# base-6u-generic-xau4.net
KiCad netlist of a schematic drawn in EAGLE
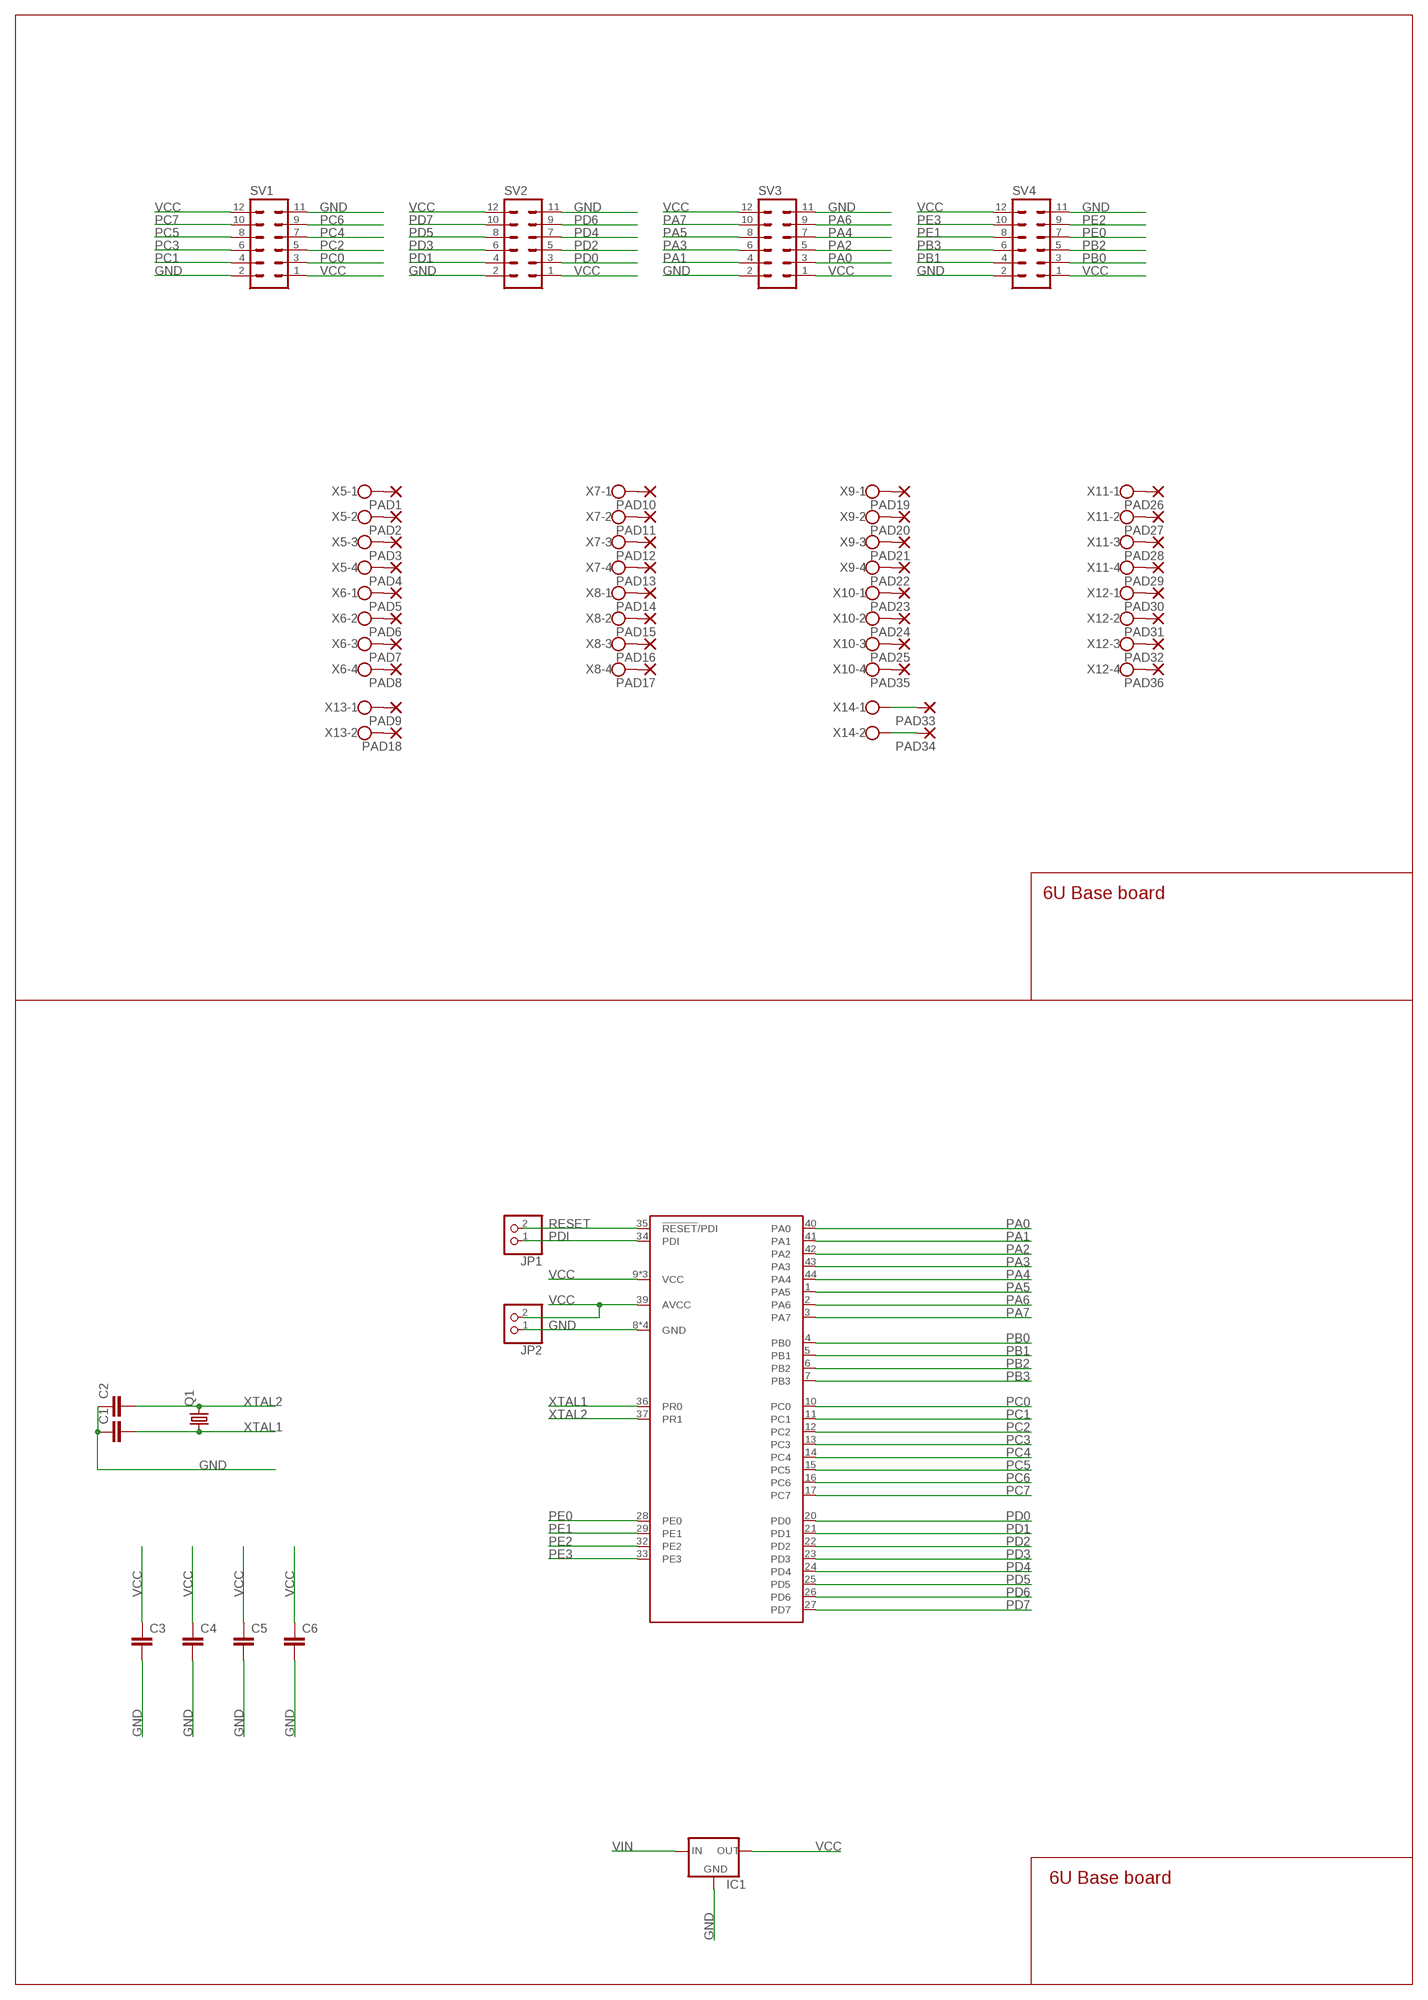
[diagram p0: schematic, sheet 1]

(export (version "E")
  (design (tool "Eeschema 10.0.6"))
  (components
    (comp (ref "C1")
      (value "C-EUC0805")
      (footprint "eagle-import:C0805")
      (libsource (lib "eagle-import") (part "C-EUC0805"))
    )
    (comp (ref "C2")
      (value "C-EUC0805")
      (footprint "eagle-import:C0805")
      (libsource (lib "eagle-import") (part "C-EUC0805"))
    )
    (comp (ref "C3")
      (value "C-EUC0603")
      (footprint "eagle-import:C0603")
      (libsource (lib "eagle-import") (part "C-EUC0603"))
    )
    (comp (ref "C4")
      (value "C-EUC0603")
      (footprint "eagle-import:C0603")
      (libsource (lib "eagle-import") (part "C-EUC0603"))
    )
    (comp (ref "C5")
      (value "C-EUC0603")
      (footprint "eagle-import:C0603")
      (libsource (lib "eagle-import") (part "C-EUC0603"))
    )
    (comp (ref "C6")
      (value "C-EUC0603")
      (footprint "eagle-import:C0603")
      (libsource (lib "eagle-import") (part "C-EUC0603"))
    )
    (comp (ref "IC1")
      (value "LM1117TO252")
      (footprint "eagle-import:TO252")
      (libsource (lib "eagle-import") (part "LM1117TO252"))
    )
    (comp (ref "JP1")
      (value "PINHD-1X2")
      (footprint "eagle-import:1X02")
      (libsource (lib "eagle-import") (part "PINHD-1X2"))
    )
    (comp (ref "JP2")
      (value "PINHD-1X2")
      (footprint "eagle-import:1X02")
      (libsource (lib "eagle-import") (part "PINHD-1X2"))
    )
    (comp (ref "PAD1")
      (value "2,54/0,8")
      (footprint "eagle-import:2,54_0,8")
      (libsource (lib "eagle-import") (part "2,54/0,8"))
    )
    (comp (ref "PAD2")
      (value "2,54/0,8")
      (footprint "eagle-import:2,54_0,8")
      (libsource (lib "eagle-import") (part "2,54/0,8"))
    )
    (comp (ref "PAD3")
      (value "2,54/0,8")
      (footprint "eagle-import:2,54_0,8")
      (libsource (lib "eagle-import") (part "2,54/0,8"))
    )
    (comp (ref "PAD4")
      (value "2,54/0,8")
      (footprint "eagle-import:2,54_0,8")
      (libsource (lib "eagle-import") (part "2,54/0,8"))
    )
    (comp (ref "PAD5")
      (value "2,54/0,8")
      (footprint "eagle-import:2,54_0,8")
      (libsource (lib "eagle-import") (part "2,54/0,8"))
    )
    (comp (ref "PAD6")
      (value "2,54/0,8")
      (footprint "eagle-import:2,54_0,8")
      (libsource (lib "eagle-import") (part "2,54/0,8"))
    )
    (comp (ref "PAD7")
      (value "2,54/0,8")
      (footprint "eagle-import:2,54_0,8")
      (libsource (lib "eagle-import") (part "2,54/0,8"))
    )
    (comp (ref "PAD8")
      (value "2,54/0,8")
      (footprint "eagle-import:2,54_0,8")
      (libsource (lib "eagle-import") (part "2,54/0,8"))
    )
    (comp (ref "PAD9")
      (value "2,54/0,8")
      (footprint "eagle-import:2,54_0,8")
      (libsource (lib "eagle-import") (part "2,54/0,8"))
    )
    (comp (ref "PAD10")
      (value "2,54/0,8")
      (footprint "eagle-import:2,54_0,8")
      (libsource (lib "eagle-import") (part "2,54/0,8"))
    )
    (comp (ref "PAD11")
      (value "2,54/0,8")
      (footprint "eagle-import:2,54_0,8")
      (libsource (lib "eagle-import") (part "2,54/0,8"))
    )
    (comp (ref "PAD12")
      (value "2,54/0,8")
      (footprint "eagle-import:2,54_0,8")
      (libsource (lib "eagle-import") (part "2,54/0,8"))
    )
    (comp (ref "PAD13")
      (value "2,54/0,8")
      (footprint "eagle-import:2,54_0,8")
      (libsource (lib "eagle-import") (part "2,54/0,8"))
    )
    (comp (ref "PAD14")
      (value "2,54/0,8")
      (footprint "eagle-import:2,54_0,8")
      (libsource (lib "eagle-import") (part "2,54/0,8"))
    )
    (comp (ref "PAD15")
      (value "2,54/0,8")
      (footprint "eagle-import:2,54_0,8")
      (libsource (lib "eagle-import") (part "2,54/0,8"))
    )
    (comp (ref "PAD16")
      (value "2,54/0,8")
      (footprint "eagle-import:2,54_0,8")
      (libsource (lib "eagle-import") (part "2,54/0,8"))
    )
    (comp (ref "PAD17")
      (value "2,54/0,8")
      (footprint "eagle-import:2,54_0,8")
      (libsource (lib "eagle-import") (part "2,54/0,8"))
    )
    (comp (ref "PAD18")
      (value "2,54/0,8")
      (footprint "eagle-import:2,54_0,8")
      (libsource (lib "eagle-import") (part "2,54/0,8"))
    )
    (comp (ref "PAD19")
      (value "2,54/0,8")
      (footprint "eagle-import:2,54_0,8")
      (libsource (lib "eagle-import") (part "2,54/0,8"))
    )
    (comp (ref "PAD20")
      (value "2,54/0,8")
      (footprint "eagle-import:2,54_0,8")
      (libsource (lib "eagle-import") (part "2,54/0,8"))
    )
    (comp (ref "PAD21")
      (value "2,54/0,8")
      (footprint "eagle-import:2,54_0,8")
      (libsource (lib "eagle-import") (part "2,54/0,8"))
    )
    (comp (ref "PAD22")
      (value "2,54/0,8")
      (footprint "eagle-import:2,54_0,8")
      (libsource (lib "eagle-import") (part "2,54/0,8"))
    )
    (comp (ref "PAD23")
      (value "2,54/0,8")
      (footprint "eagle-import:2,54_0,8")
      (libsource (lib "eagle-import") (part "2,54/0,8"))
    )
    (comp (ref "PAD24")
      (value "2,54/0,8")
      (footprint "eagle-import:2,54_0,8")
      (libsource (lib "eagle-import") (part "2,54/0,8"))
    )
    (comp (ref "PAD25")
      (value "2,54/0,8")
      (footprint "eagle-import:2,54_0,8")
      (libsource (lib "eagle-import") (part "2,54/0,8"))
    )
    (comp (ref "PAD26")
      (value "2,54/0,8")
      (footprint "eagle-import:2,54_0,8")
      (libsource (lib "eagle-import") (part "2,54/0,8"))
    )
    (comp (ref "PAD27")
      (value "2,54/0,8")
      (footprint "eagle-import:2,54_0,8")
      (libsource (lib "eagle-import") (part "2,54/0,8"))
    )
    (comp (ref "PAD28")
      (value "2,54/0,8")
      (footprint "eagle-import:2,54_0,8")
      (libsource (lib "eagle-import") (part "2,54/0,8"))
    )
    (comp (ref "PAD29")
      (value "2,54/0,8")
      (footprint "eagle-import:2,54_0,8")
      (libsource (lib "eagle-import") (part "2,54/0,8"))
    )
    (comp (ref "PAD30")
      (value "2,54/0,8")
      (footprint "eagle-import:2,54_0,8")
      (libsource (lib "eagle-import") (part "2,54/0,8"))
    )
    (comp (ref "PAD31")
      (value "2,54/0,8")
      (footprint "eagle-import:2,54_0,8")
      (libsource (lib "eagle-import") (part "2,54/0,8"))
    )
    (comp (ref "PAD32")
      (value "2,54/0,8")
      (footprint "eagle-import:2,54_0,8")
      (libsource (lib "eagle-import") (part "2,54/0,8"))
    )
    (comp (ref "PAD33")
      (value "2,54/0,8")
      (footprint "eagle-import:2,54_0,8")
      (libsource (lib "eagle-import") (part "2,54/0,8"))
    )
    (comp (ref "PAD34")
      (value "2,54/0,8")
      (footprint "eagle-import:2,54_0,8")
      (libsource (lib "eagle-import") (part "2,54/0,8"))
    )
    (comp (ref "PAD35")
      (value "2,54/0,8")
      (footprint "eagle-import:2,54_0,8")
      (libsource (lib "eagle-import") (part "2,54/0,8"))
    )
    (comp (ref "PAD36")
      (value "2,54/0,8")
      (footprint "eagle-import:2,54_0,8")
      (libsource (lib "eagle-import") (part "2,54/0,8"))
    )
    (comp (ref "Q1")
      (value "CRYSTALHC49S")
      (footprint "eagle-import:HC49_S")
      (libsource (lib "eagle-import") (part "CRYSTALHC49S"))
    )
    (comp (ref "SV1")
      (value "MA06-2")
      (footprint "eagle-import:MA06-2")
      (libsource (lib "eagle-import") (part "MA06-2"))
    )
    (comp (ref "SV2")
      (value "MA06-2")
      (footprint "eagle-import:MA06-2")
      (libsource (lib "eagle-import") (part "MA06-2"))
    )
    (comp (ref "SV3")
      (value "MA06-2")
      (footprint "eagle-import:MA06-2")
      (libsource (lib "eagle-import") (part "MA06-2"))
    )
    (comp (ref "SV4")
      (value "MA06-2")
      (footprint "eagle-import:MA06-2")
      (libsource (lib "eagle-import") (part "MA06-2"))
    )
    (comp (ref "U1")
      (value "ATXMEGA32A4U-AU")
      (footprint "eagle-import:TQFP-44A-44")
      (libsource (lib "eagle-import") (part "ATXMEGA32A4U-AU"))
    )
    (comp (ref "X5")
      (value "W237-4")
      (footprint "eagle-import:W237-4")
      (libsource (lib "eagle-import") (part "W237-4"))
    )
    (comp (ref "X6")
      (value "W237-4")
      (footprint "eagle-import:W237-4")
      (libsource (lib "eagle-import") (part "W237-4"))
    )
    (comp (ref "X7")
      (value "W237-4")
      (footprint "eagle-import:W237-4")
      (libsource (lib "eagle-import") (part "W237-4"))
    )
    (comp (ref "X8")
      (value "W237-4")
      (footprint "eagle-import:W237-4")
      (libsource (lib "eagle-import") (part "W237-4"))
    )
    (comp (ref "X9")
      (value "W237-4")
      (footprint "eagle-import:W237-4")
      (libsource (lib "eagle-import") (part "W237-4"))
    )
    (comp (ref "X10")
      (value "W237-4")
      (footprint "eagle-import:W237-4")
      (libsource (lib "eagle-import") (part "W237-4"))
    )
    (comp (ref "X11")
      (value "W237-4")
      (footprint "eagle-import:W237-4")
      (libsource (lib "eagle-import") (part "W237-4"))
    )
    (comp (ref "X12")
      (value "W237-4")
      (footprint "eagle-import:W237-4")
      (libsource (lib "eagle-import") (part "W237-4"))
    )
    (comp (ref "X13")
      (value "W237-102")
      (footprint "eagle-import:W237-102")
      (fields (field (name "MPN") "237-102"))
      (libsource (lib "eagle-import") (part "W237-102"))
    )
    (comp (ref "X14")
      (value "W237-102")
      (footprint "eagle-import:W237-102")
      (fields (field (name "MPN") "237-102"))
      (libsource (lib "eagle-import") (part "W237-102"))
    )
  )
  (nets
    (net (code "1") (name "/GND") (class "Default")
      (node (ref "C1") (pin "1") (pinfunction "1_1") (pintype "passive"))
      (node (ref "C2") (pin "1") (pinfunction "1_1") (pintype "passive"))
      (node (ref "C3") (pin "2") (pinfunction "2_2") (pintype "passive"))
      (node (ref "C4") (pin "2") (pinfunction "2_2") (pintype "passive"))
      (node (ref "C5") (pin "2") (pinfunction "2_2") (pintype "passive"))
      (node (ref "C6") (pin "2") (pinfunction "2_2") (pintype "passive"))
      (node (ref "IC1") (pin "1") (pinfunction "GND_1") (pintype "input"))
      (node (ref "JP2") (pin "1") (pinfunction "1_1") (pintype "passive"))
      (node (ref "PAD33") (pin "1") (pinfunction "P_1") (pintype "passive"))
      (node (ref "SV1") (pin "11") (pinfunction "11_11") (pintype "passive"))
      (node (ref "SV1") (pin "2") (pinfunction "2_2") (pintype "passive"))
      (node (ref "SV2") (pin "11") (pinfunction "11_11") (pintype "passive"))
      (node (ref "SV2") (pin "2") (pinfunction "2_2") (pintype "passive"))
      (node (ref "SV3") (pin "11") (pinfunction "11_11") (pintype "passive"))
      (node (ref "SV3") (pin "2") (pinfunction "2_2") (pintype "passive"))
      (node (ref "SV4") (pin "11") (pinfunction "11_11") (pintype "passive"))
      (node (ref "SV4") (pin "2") (pinfunction "2_2") (pintype "passive"))
      (node (ref "U1") (pin "18") (pinfunction "GND_18") (pintype "power_in"))
      (node (ref "U1") (pin "30") (pinfunction "GND_30") (pintype "power_in"))
      (node (ref "U1") (pin "38") (pinfunction "GND_38") (pintype "power_in"))
      (node (ref "U1") (pin "8") (pinfunction "GND_8") (pintype "power_in"))
      (node (ref "X14") (pin "1") (pinfunction "KL_1") (pintype "passive"))
    )
    (net (code "2") (name "/PA0") (class "Default")
      (node (ref "SV3") (pin "3") (pinfunction "3_3") (pintype "passive"))
      (node (ref "U1") (pin "40") (pinfunction "PA0_40") (pintype "bidirectional"))
    )
    (net (code "3") (name "/PA1") (class "Default")
      (node (ref "SV3") (pin "4") (pinfunction "4_4") (pintype "passive"))
      (node (ref "U1") (pin "41") (pinfunction "PA1_41") (pintype "bidirectional"))
    )
    (net (code "4") (name "/PA2") (class "Default")
      (node (ref "SV3") (pin "5") (pinfunction "5_5") (pintype "passive"))
      (node (ref "U1") (pin "42") (pinfunction "PA2_42") (pintype "bidirectional"))
    )
    (net (code "5") (name "/PA3") (class "Default")
      (node (ref "SV3") (pin "6") (pinfunction "6_6") (pintype "passive"))
      (node (ref "U1") (pin "43") (pinfunction "PA3_43") (pintype "bidirectional"))
    )
    (net (code "6") (name "/PA4") (class "Default")
      (node (ref "SV3") (pin "7") (pinfunction "7_7") (pintype "passive"))
      (node (ref "U1") (pin "44") (pinfunction "PA4_44") (pintype "bidirectional"))
    )
    (net (code "7") (name "/PA5") (class "Default")
      (node (ref "SV3") (pin "8") (pinfunction "8_8") (pintype "passive"))
      (node (ref "U1") (pin "1") (pinfunction "PA5_1") (pintype "bidirectional"))
    )
    (net (code "8") (name "/PA6") (class "Default")
      (node (ref "SV3") (pin "9") (pinfunction "9_9") (pintype "passive"))
      (node (ref "U1") (pin "2") (pinfunction "PA6_2") (pintype "bidirectional"))
    )
    (net (code "9") (name "/PA7") (class "Default")
      (node (ref "SV3") (pin "10") (pinfunction "10_10") (pintype "passive"))
      (node (ref "U1") (pin "3") (pinfunction "PA7_3") (pintype "bidirectional"))
    )
    (net (code "10") (name "/PB0") (class "Default")
      (node (ref "SV4") (pin "3") (pinfunction "3_3") (pintype "passive"))
      (node (ref "U1") (pin "4") (pinfunction "PB0_4") (pintype "bidirectional"))
    )
    (net (code "11") (name "/PB1") (class "Default")
      (node (ref "SV4") (pin "4") (pinfunction "4_4") (pintype "passive"))
      (node (ref "U1") (pin "5") (pinfunction "PB1_5") (pintype "bidirectional"))
    )
    (net (code "12") (name "/PB2") (class "Default")
      (node (ref "SV4") (pin "5") (pinfunction "5_5") (pintype "passive"))
      (node (ref "U1") (pin "6") (pinfunction "PB2_6") (pintype "bidirectional"))
    )
    (net (code "13") (name "/PB3") (class "Default")
      (node (ref "SV4") (pin "6") (pinfunction "6_6") (pintype "passive"))
      (node (ref "U1") (pin "7") (pinfunction "PB3_7") (pintype "bidirectional"))
    )
    (net (code "14") (name "/PC0") (class "Default")
      (node (ref "SV1") (pin "3") (pinfunction "3_3") (pintype "passive"))
      (node (ref "U1") (pin "10") (pinfunction "PC0_10") (pintype "bidirectional"))
    )
    (net (code "15") (name "/PC1") (class "Default")
      (node (ref "SV1") (pin "4") (pinfunction "4_4") (pintype "passive"))
      (node (ref "U1") (pin "11") (pinfunction "PC1_11") (pintype "bidirectional"))
    )
    (net (code "16") (name "/PC2") (class "Default")
      (node (ref "SV1") (pin "5") (pinfunction "5_5") (pintype "passive"))
      (node (ref "U1") (pin "12") (pinfunction "PC2_12") (pintype "bidirectional"))
    )
    (net (code "17") (name "/PC3") (class "Default")
      (node (ref "SV1") (pin "6") (pinfunction "6_6") (pintype "passive"))
      (node (ref "U1") (pin "13") (pinfunction "PC3_13") (pintype "bidirectional"))
    )
    (net (code "18") (name "/PC4") (class "Default")
      (node (ref "SV1") (pin "7") (pinfunction "7_7") (pintype "passive"))
      (node (ref "U1") (pin "14") (pinfunction "PC4_14") (pintype "bidirectional"))
    )
    (net (code "19") (name "/PC5") (class "Default")
      (node (ref "SV1") (pin "8") (pinfunction "8_8") (pintype "passive"))
      (node (ref "U1") (pin "15") (pinfunction "PC5_15") (pintype "bidirectional"))
    )
    (net (code "20") (name "/PC6") (class "Default")
      (node (ref "SV1") (pin "9") (pinfunction "9_9") (pintype "passive"))
      (node (ref "U1") (pin "16") (pinfunction "PC6_16") (pintype "bidirectional"))
    )
    (net (code "21") (name "/PC7") (class "Default")
      (node (ref "SV1") (pin "10") (pinfunction "10_10") (pintype "passive"))
      (node (ref "U1") (pin "17") (pinfunction "PC7_17") (pintype "bidirectional"))
    )
    (net (code "22") (name "/PD0") (class "Default")
      (node (ref "SV2") (pin "3") (pinfunction "3_3") (pintype "passive"))
      (node (ref "U1") (pin "20") (pinfunction "PD0_20") (pintype "bidirectional"))
    )
    (net (code "23") (name "/PD1") (class "Default")
      (node (ref "SV2") (pin "4") (pinfunction "4_4") (pintype "passive"))
      (node (ref "U1") (pin "21") (pinfunction "PD1_21") (pintype "bidirectional"))
    )
    (net (code "24") (name "/PD2") (class "Default")
      (node (ref "SV2") (pin "5") (pinfunction "5_5") (pintype "passive"))
      (node (ref "U1") (pin "22") (pinfunction "PD2_22") (pintype "bidirectional"))
    )
    (net (code "25") (name "/PD3") (class "Default")
      (node (ref "SV2") (pin "6") (pinfunction "6_6") (pintype "passive"))
      (node (ref "U1") (pin "23") (pinfunction "PD3_23") (pintype "bidirectional"))
    )
    (net (code "26") (name "/PD4") (class "Default")
      (node (ref "SV2") (pin "7") (pinfunction "7_7") (pintype "passive"))
      (node (ref "U1") (pin "24") (pinfunction "PD4_24") (pintype "bidirectional"))
    )
    (net (code "27") (name "/PD5") (class "Default")
      (node (ref "SV2") (pin "8") (pinfunction "8_8") (pintype "passive"))
      (node (ref "U1") (pin "25") (pinfunction "PD5_25") (pintype "bidirectional"))
    )
    (net (code "28") (name "/PD6") (class "Default")
      (node (ref "SV2") (pin "9") (pinfunction "9_9") (pintype "passive"))
      (node (ref "U1") (pin "26") (pinfunction "PD6_26") (pintype "bidirectional"))
    )
    (net (code "29") (name "/PD7") (class "Default")
      (node (ref "SV2") (pin "10") (pinfunction "10_10") (pintype "passive"))
      (node (ref "U1") (pin "27") (pinfunction "PD7_27") (pintype "bidirectional"))
    )
    (net (code "30") (name "/PDI") (class "Default")
      (node (ref "JP1") (pin "1") (pinfunction "1_1") (pintype "passive"))
      (node (ref "U1") (pin "34") (pinfunction "PDI_34") (pintype "bidirectional"))
    )
    (net (code "31") (name "/PE0") (class "Default")
      (node (ref "SV4") (pin "7") (pinfunction "7_7") (pintype "passive"))
      (node (ref "U1") (pin "28") (pinfunction "PE0_28") (pintype "bidirectional"))
    )
    (net (code "32") (name "/PE1") (class "Default")
      (node (ref "SV4") (pin "8") (pinfunction "8_8") (pintype "passive"))
      (node (ref "U1") (pin "29") (pinfunction "PE1_29") (pintype "bidirectional"))
    )
    (net (code "33") (name "/PE2") (class "Default")
      (node (ref "SV4") (pin "9") (pinfunction "9_9") (pintype "passive"))
      (node (ref "U1") (pin "32") (pinfunction "PE2_32") (pintype "bidirectional"))
    )
    (net (code "34") (name "/PE3") (class "Default")
      (node (ref "SV4") (pin "10") (pinfunction "10_10") (pintype "passive"))
      (node (ref "U1") (pin "33") (pinfunction "PE3_33") (pintype "bidirectional"))
    )
    (net (code "35") (name "/RESET") (class "Default")
      (node (ref "JP1") (pin "2") (pinfunction "2_2") (pintype "passive"))
      (node (ref "U1") (pin "35") (pinfunction "~{RESET}/PDI_35") (pintype "bidirectional"))
    )
    (net (code "36") (name "/VCC") (class "Default")
      (node (ref "C3") (pin "1") (pinfunction "1_1") (pintype "passive"))
      (node (ref "C4") (pin "1") (pinfunction "1_1") (pintype "passive"))
      (node (ref "C5") (pin "1") (pinfunction "1_1") (pintype "passive"))
      (node (ref "C6") (pin "1") (pinfunction "1_1") (pintype "passive"))
      (node (ref "IC1") (pin "3") (pinfunction "OUT_3") (pintype "passive"))
      (node (ref "JP2") (pin "2") (pinfunction "2_2") (pintype "passive"))
      (node (ref "SV1") (pin "1") (pinfunction "1_1") (pintype "passive"))
      (node (ref "SV1") (pin "12") (pinfunction "12_12") (pintype "passive"))
      (node (ref "SV2") (pin "1") (pinfunction "1_1") (pintype "passive"))
      (node (ref "SV2") (pin "12") (pinfunction "12_12") (pintype "passive"))
      (node (ref "SV3") (pin "1") (pinfunction "1_1") (pintype "passive"))
      (node (ref "SV3") (pin "12") (pinfunction "12_12") (pintype "passive"))
      (node (ref "SV4") (pin "1") (pinfunction "1_1") (pintype "passive"))
      (node (ref "SV4") (pin "12") (pinfunction "12_12") (pintype "passive"))
      (node (ref "U1") (pin "19") (pinfunction "VCC_19") (pintype "power_in"))
      (node (ref "U1") (pin "31") (pinfunction "VCC_31") (pintype "power_in"))
      (node (ref "U1") (pin "39") (pinfunction "AVCC_39") (pintype "power_in"))
      (node (ref "U1") (pin "9") (pinfunction "VCC_9") (pintype "power_in"))
    )
    (net (code "37") (name "/VIN") (class "Default")
      (node (ref "IC1") (pin "2") (pinfunction "IN_2") (pintype "input"))
      (node (ref "PAD34") (pin "1") (pinfunction "P_1") (pintype "passive"))
      (node (ref "X14") (pin "2") (pinfunction "KL_2") (pintype "passive"))
    )
    (net (code "38") (name "/XTAL1") (class "Default")
      (node (ref "C1") (pin "2") (pinfunction "2_2") (pintype "passive"))
      (node (ref "Q1") (pin "1") (pinfunction "1_1") (pintype "passive"))
      (node (ref "U1") (pin "36") (pinfunction "PR0_36") (pintype "bidirectional"))
    )
    (net (code "39") (name "/XTAL2") (class "Default")
      (node (ref "C2") (pin "2") (pinfunction "2_2") (pintype "passive"))
      (node (ref "Q1") (pin "2") (pinfunction "2_2") (pintype "passive"))
      (node (ref "U1") (pin "37") (pinfunction "PR1_37") (pintype "bidirectional"))
    )
    (net (code "40") (name "Net-(PAD1-P)") (class "Default")
      (node (ref "PAD1") (pin "1") (pinfunction "P_1") (pintype "passive"))
      (node (ref "X5") (pin "1") (pinfunction "KL_1") (pintype "passive"))
    )
    (net (code "41") (name "Net-(PAD2-P)") (class "Default")
      (node (ref "PAD2") (pin "1") (pinfunction "P_1") (pintype "passive"))
      (node (ref "X5") (pin "2") (pinfunction "KL_2") (pintype "passive"))
    )
    (net (code "42") (name "Net-(PAD3-P)") (class "Default")
      (node (ref "PAD3") (pin "1") (pinfunction "P_1") (pintype "passive"))
      (node (ref "X5") (pin "3") (pinfunction "KL_3") (pintype "passive"))
    )
    (net (code "43") (name "Net-(PAD4-P)") (class "Default")
      (node (ref "PAD4") (pin "1") (pinfunction "P_1") (pintype "passive"))
      (node (ref "X5") (pin "4") (pinfunction "KL_4") (pintype "passive"))
    )
    (net (code "44") (name "Net-(PAD5-P)") (class "Default")
      (node (ref "PAD5") (pin "1") (pinfunction "P_1") (pintype "passive"))
      (node (ref "X6") (pin "1") (pinfunction "KL_1") (pintype "passive"))
    )
    (net (code "45") (name "Net-(PAD6-P)") (class "Default")
      (node (ref "PAD6") (pin "1") (pinfunction "P_1") (pintype "passive"))
      (node (ref "X6") (pin "2") (pinfunction "KL_2") (pintype "passive"))
    )
    (net (code "46") (name "Net-(PAD7-P)") (class "Default")
      (node (ref "PAD7") (pin "1") (pinfunction "P_1") (pintype "passive"))
      (node (ref "X6") (pin "3") (pinfunction "KL_3") (pintype "passive"))
    )
    (net (code "47") (name "Net-(PAD8-P)") (class "Default")
      (node (ref "PAD8") (pin "1") (pinfunction "P_1") (pintype "passive"))
      (node (ref "X6") (pin "4") (pinfunction "KL_4") (pintype "passive"))
    )
    (net (code "48") (name "Net-(PAD9-P)") (class "Default")
      (node (ref "PAD9") (pin "1") (pinfunction "P_1") (pintype "passive"))
      (node (ref "X13") (pin "1") (pinfunction "KL_1") (pintype "passive"))
    )
    (net (code "49") (name "Net-(PAD10-P)") (class "Default")
      (node (ref "PAD10") (pin "1") (pinfunction "P_1") (pintype "passive"))
      (node (ref "X7") (pin "1") (pinfunction "KL_1") (pintype "passive"))
    )
    (net (code "50") (name "Net-(PAD11-P)") (class "Default")
      (node (ref "PAD11") (pin "1") (pinfunction "P_1") (pintype "passive"))
      (node (ref "X7") (pin "2") (pinfunction "KL_2") (pintype "passive"))
    )
    (net (code "51") (name "Net-(PAD12-P)") (class "Default")
      (node (ref "PAD12") (pin "1") (pinfunction "P_1") (pintype "passive"))
      (node (ref "X7") (pin "3") (pinfunction "KL_3") (pintype "passive"))
    )
    (net (code "52") (name "Net-(PAD13-P)") (class "Default")
      (node (ref "PAD13") (pin "1") (pinfunction "P_1") (pintype "passive"))
      (node (ref "X7") (pin "4") (pinfunction "KL_4") (pintype "passive"))
    )
    (net (code "53") (name "Net-(PAD14-P)") (class "Default")
      (node (ref "PAD14") (pin "1") (pinfunction "P_1") (pintype "passive"))
      (node (ref "X8") (pin "1") (pinfunction "KL_1") (pintype "passive"))
    )
    (net (code "54") (name "Net-(PAD15-P)") (class "Default")
      (node (ref "PAD15") (pin "1") (pinfunction "P_1") (pintype "passive"))
      (node (ref "X8") (pin "2") (pinfunction "KL_2") (pintype "passive"))
    )
    (net (code "55") (name "Net-(PAD16-P)") (class "Default")
      (node (ref "PAD16") (pin "1") (pinfunction "P_1") (pintype "passive"))
      (node (ref "X8") (pin "3") (pinfunction "KL_3") (pintype "passive"))
    )
    (net (code "56") (name "Net-(PAD17-P)") (class "Default")
      (node (ref "PAD17") (pin "1") (pinfunction "P_1") (pintype "passive"))
      (node (ref "X8") (pin "4") (pinfunction "KL_4") (pintype "passive"))
    )
    (net (code "57") (name "Net-(PAD18-P)") (class "Default")
      (node (ref "PAD18") (pin "1") (pinfunction "P_1") (pintype "passive"))
      (node (ref "X13") (pin "2") (pinfunction "KL_2") (pintype "passive"))
    )
    (net (code "58") (name "Net-(PAD19-P)") (class "Default")
      (node (ref "PAD19") (pin "1") (pinfunction "P_1") (pintype "passive"))
      (node (ref "X9") (pin "1") (pinfunction "KL_1") (pintype "passive"))
    )
    (net (code "59") (name "Net-(PAD20-P)") (class "Default")
      (node (ref "PAD20") (pin "1") (pinfunction "P_1") (pintype "passive"))
      (node (ref "X9") (pin "2") (pinfunction "KL_2") (pintype "passive"))
    )
    (net (code "60") (name "Net-(PAD21-P)") (class "Default")
      (node (ref "PAD21") (pin "1") (pinfunction "P_1") (pintype "passive"))
      (node (ref "X9") (pin "3") (pinfunction "KL_3") (pintype "passive"))
    )
    (net (code "61") (name "Net-(PAD22-P)") (class "Default")
      (node (ref "PAD22") (pin "1") (pinfunction "P_1") (pintype "passive"))
      (node (ref "X9") (pin "4") (pinfunction "KL_4") (pintype "passive"))
    )
    (net (code "62") (name "Net-(PAD23-P)") (class "Default")
      (node (ref "PAD23") (pin "1") (pinfunction "P_1") (pintype "passive"))
      (node (ref "X10") (pin "1") (pinfunction "KL_1") (pintype "passive"))
    )
    (net (code "63") (name "Net-(PAD24-P)") (class "Default")
      (node (ref "PAD24") (pin "1") (pinfunction "P_1") (pintype "passive"))
      (node (ref "X10") (pin "2") (pinfunction "KL_2") (pintype "passive"))
    )
    (net (code "64") (name "Net-(PAD25-P)") (class "Default")
      (node (ref "PAD25") (pin "1") (pinfunction "P_1") (pintype "passive"))
      (node (ref "X10") (pin "3") (pinfunction "KL_3") (pintype "passive"))
    )
    (net (code "65") (name "Net-(PAD26-P)") (class "Default")
      (node (ref "PAD26") (pin "1") (pinfunction "P_1") (pintype "passive"))
      (node (ref "X11") (pin "1") (pinfunction "KL_1") (pintype "passive"))
    )
    (net (code "66") (name "Net-(PAD27-P)") (class "Default")
      (node (ref "PAD27") (pin "1") (pinfunction "P_1") (pintype "passive"))
      (node (ref "X11") (pin "2") (pinfunction "KL_2") (pintype "passive"))
    )
    (net (code "67") (name "Net-(PAD28-P)") (class "Default")
      (node (ref "PAD28") (pin "1") (pinfunction "P_1") (pintype "passive"))
      (node (ref "X11") (pin "3") (pinfunction "KL_3") (pintype "passive"))
    )
    (net (code "68") (name "Net-(PAD29-P)") (class "Default")
      (node (ref "PAD29") (pin "1") (pinfunction "P_1") (pintype "passive"))
      (node (ref "X11") (pin "4") (pinfunction "KL_4") (pintype "passive"))
    )
    (net (code "69") (name "Net-(PAD30-P)") (class "Default")
      (node (ref "PAD30") (pin "1") (pinfunction "P_1") (pintype "passive"))
      (node (ref "X12") (pin "1") (pinfunction "KL_1") (pintype "passive"))
    )
    (net (code "70") (name "Net-(PAD31-P)") (class "Default")
      (node (ref "PAD31") (pin "1") (pinfunction "P_1") (pintype "passive"))
      (node (ref "X12") (pin "2") (pinfunction "KL_2") (pintype "passive"))
    )
    (net (code "71") (name "Net-(PAD32-P)") (class "Default")
      (node (ref "PAD32") (pin "1") (pinfunction "P_1") (pintype "passive"))
      (node (ref "X12") (pin "3") (pinfunction "KL_3") (pintype "passive"))
    )
    (net (code "72") (name "Net-(PAD35-P)") (class "Default")
      (node (ref "PAD35") (pin "1") (pinfunction "P_1") (pintype "passive"))
      (node (ref "X10") (pin "4") (pinfunction "KL_4") (pintype "passive"))
    )
    (net (code "73") (name "Net-(PAD36-P)") (class "Default")
      (node (ref "PAD36") (pin "1") (pinfunction "P_1") (pintype "passive"))
      (node (ref "X12") (pin "4") (pinfunction "KL_4") (pintype "passive"))
    )
  )
)
